# Rumyantsev.net
KiCad netlist of a schematic drawn in EasyEDA
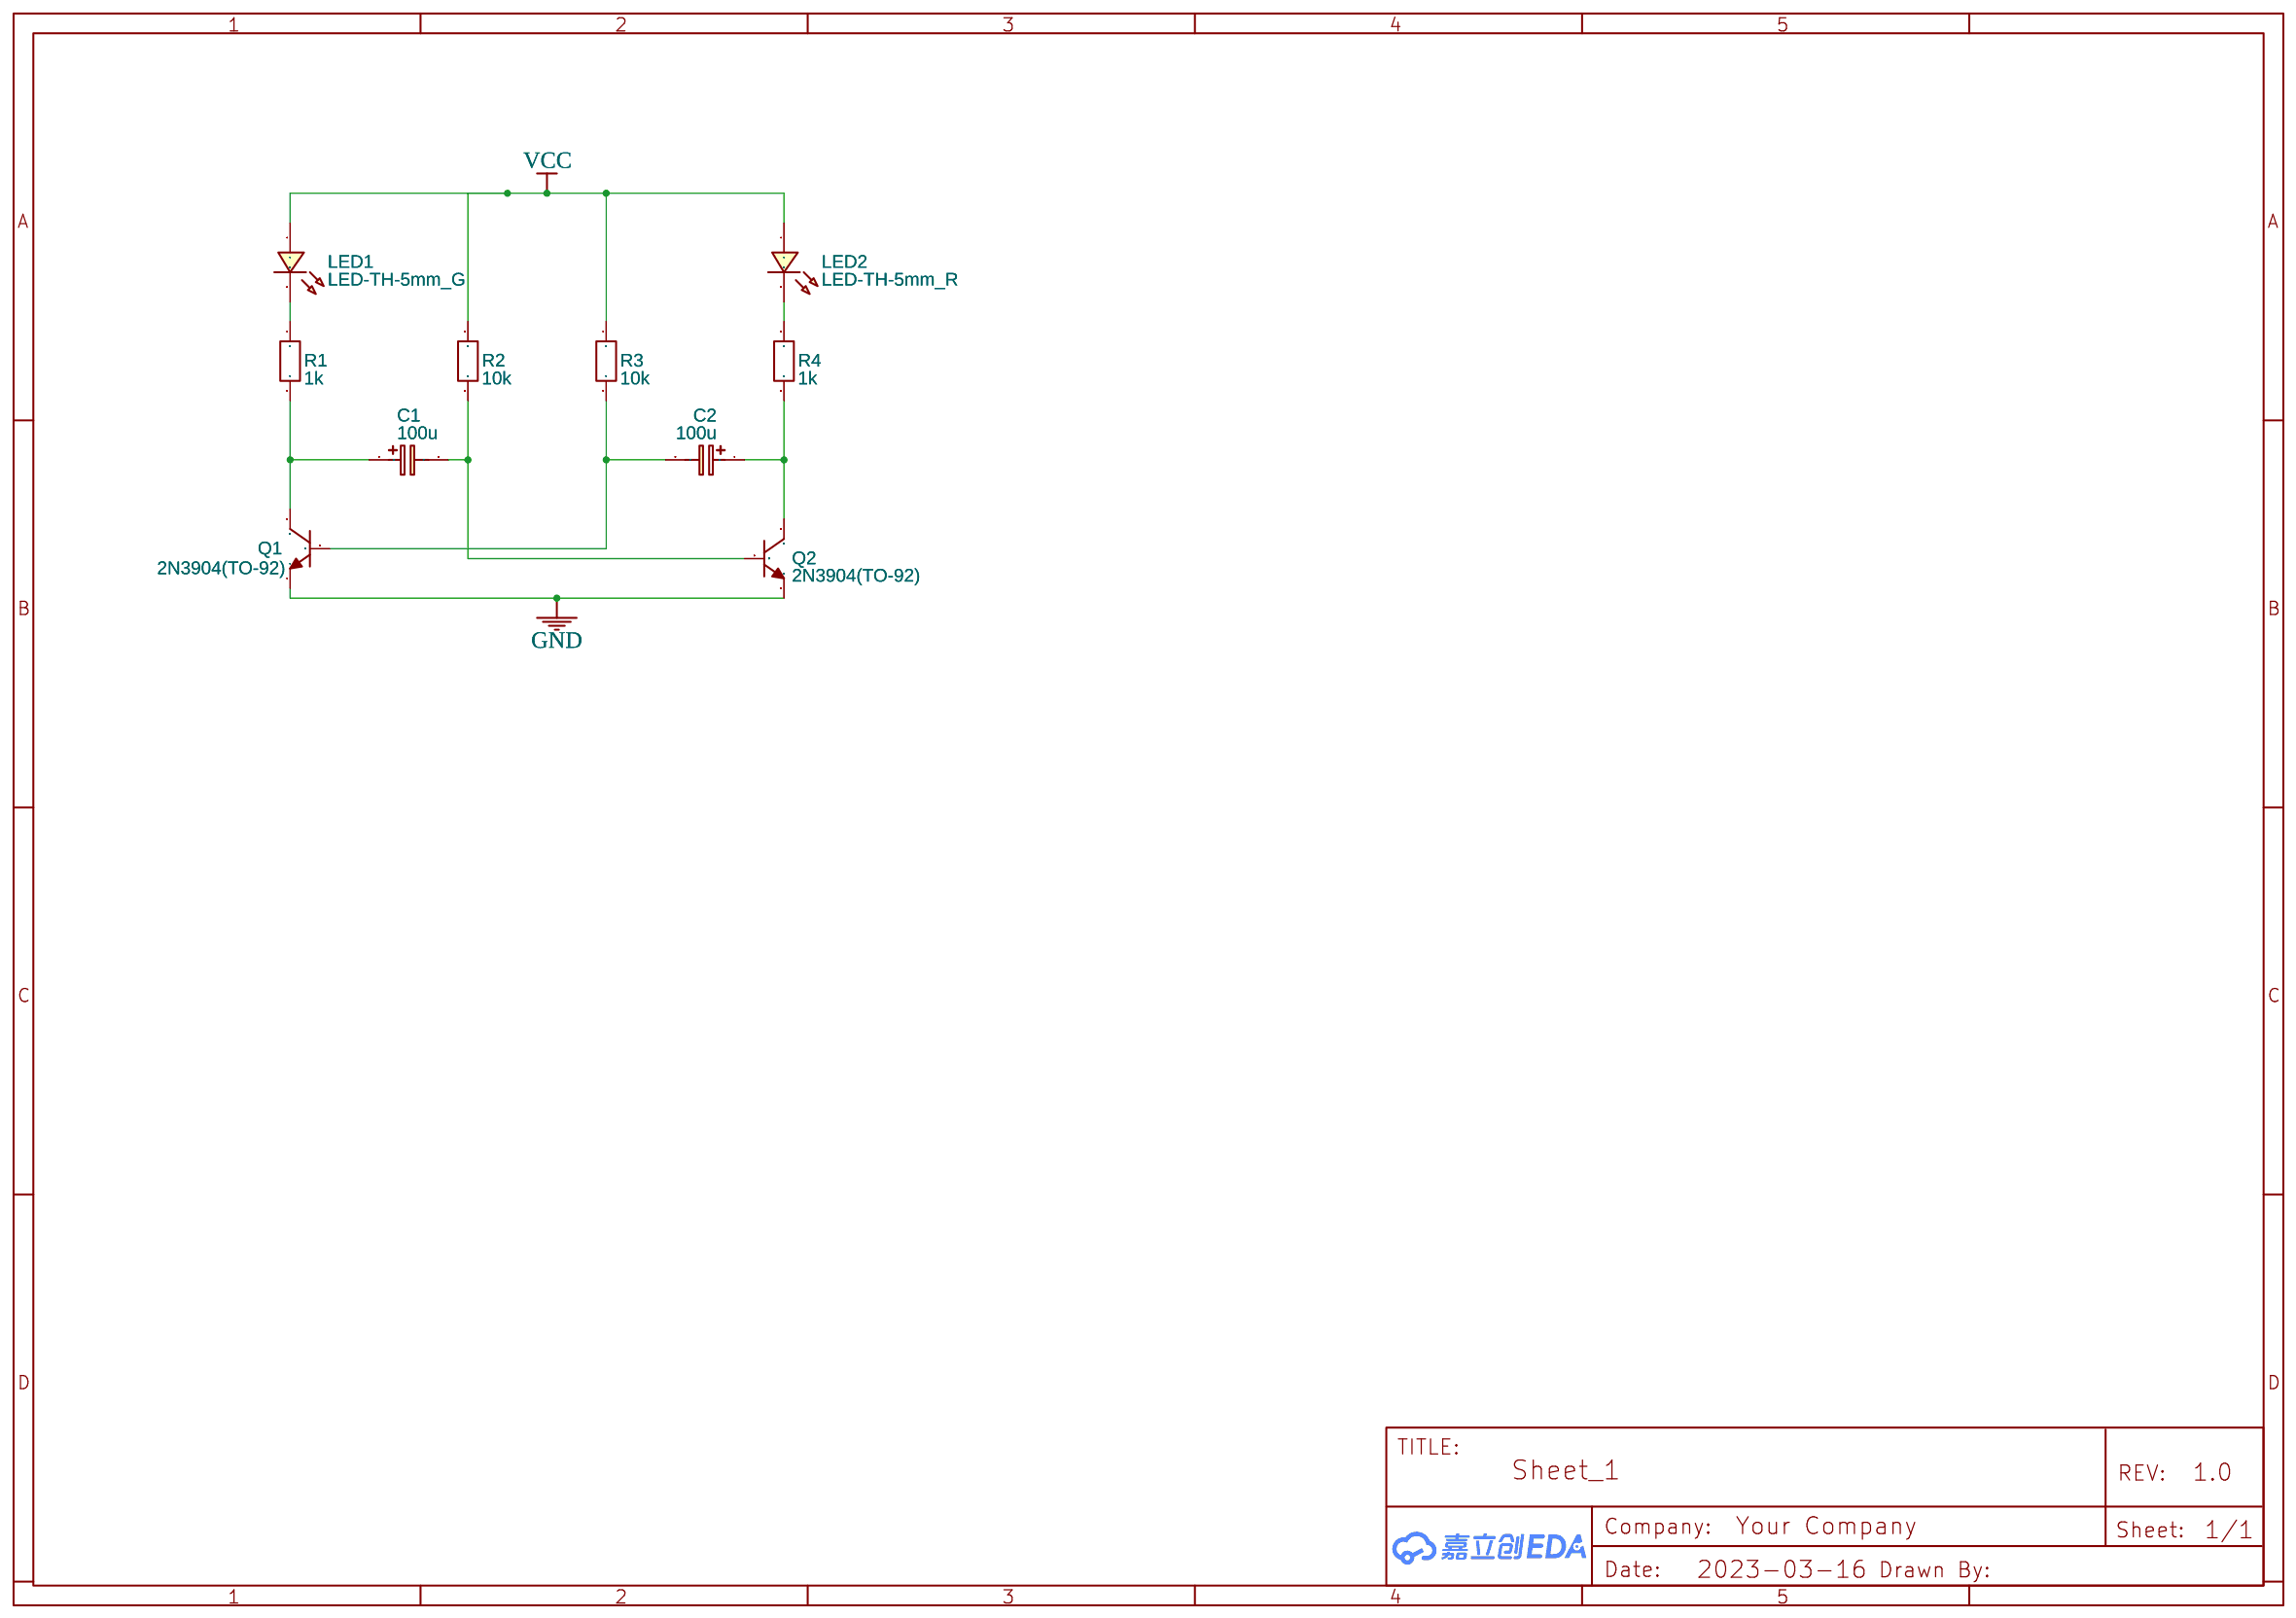
[diagram p0: schematic sheet]

(export (version "E")
  (design (tool "Eeschema 10.0.6"))
  (components
    (comp (ref "C1") (value "100u") (libsource (lib "") (part "CE_TH_D6.3×F2.5_EU")))
    (comp (ref "C2") (value "100u") (libsource (lib "") (part "CE_TH_D6.3×F2.5_EU_1")))
    (comp (ref "LED1")
      (value "LED-TH-5mm_G")
      (fields
        (field (name "BOM_Manufacturer Part") "333-2SYGD/S530-E2")
        (field (name "BOM_Supplier Part") "C88163")
      )
      (libsource (lib "") (part "LED-TH-5mm_G"))
    )
    (comp (ref "LED2")
      (value "LED-TH-5mm_R")
      (fields
        (field (name "BOM_Manufacturer Part") "333-2SURD/S530-A3")
        (field (name "BOM_Supplier Part") "C87271")
      )
      (libsource (lib "") (part "LED-TH-5mm_R"))
    )
    (comp (ref "Q1")
      (value "2N3904(TO-92)")
      (fields (field (name "BOM_Manufacturer Part") "2N3904") (field (name "BOM_Supplier Part") "C118538"))
      (libsource (lib "") (part "2N3904(TO-92)_1"))
    )
    (comp (ref "Q2")
      (value "2N3904(TO-92)")
      (fields (field (name "BOM_Manufacturer Part") "2N3904") (field (name "BOM_Supplier Part") "C118538"))
      (libsource (lib "") (part "2N3904(TO-92)"))
    )
    (comp (ref "R1") (value "1k") (libsource (lib "") (part "R_AXIAL-0.4_EU")))
    (comp (ref "R2") (value "10k") (libsource (lib "") (part "R_AXIAL-0.4_EU")))
    (comp (ref "R3") (value "10k") (libsource (lib "") (part "R_AXIAL-0.4_EU")))
    (comp (ref "R4") (value "1k") (libsource (lib "") (part "R_AXIAL-0.4_EU")))
  )
  (nets
    (net (code "1") (name "GND") (class "Default")
      (node (ref "Q1") (pin "1") (pinfunction "E_1") (pintype "unspecified"))
      (node (ref "Q2") (pin "1") (pinfunction "E_1") (pintype "unspecified"))
    )
    (net (code "2") (name "Net-(LED1-Pad2)") (class "Default")
      (node (ref "LED1") (pin "2") (pinfunction "2_2") (pintype "unspecified"))
      (node (ref "R1") (pin "1") (pinfunction "1_1") (pintype "unspecified"))
    )
    (net (code "3") (name "Net-(LED2-Pad2)") (class "Default")
      (node (ref "LED2") (pin "2") (pinfunction "2_2") (pintype "unspecified"))
      (node (ref "R4") (pin "1") (pinfunction "1_1") (pintype "unspecified"))
    )
    (net (code "4") (name "Net-(Q1-B)") (class "Default")
      (node (ref "C2") (pin "2") (pinfunction "2_2") (pintype "unspecified"))
      (node (ref "Q1") (pin "2") (pinfunction "B_2") (pintype "unspecified"))
      (node (ref "R3") (pin "2") (pinfunction "2_2") (pintype "unspecified"))
    )
    (net (code "5") (name "Net-(Q1-C)") (class "Default")
      (node (ref "C1") (pin "1") (pinfunction "1_1") (pintype "unspecified"))
      (node (ref "Q1") (pin "3") (pinfunction "C_3") (pintype "unspecified"))
      (node (ref "R1") (pin "2") (pinfunction "2_2") (pintype "unspecified"))
    )
    (net (code "6") (name "Net-(Q2-B)") (class "Default")
      (node (ref "C1") (pin "2") (pinfunction "2_2") (pintype "unspecified"))
      (node (ref "Q2") (pin "2") (pinfunction "B_2") (pintype "unspecified"))
      (node (ref "R2") (pin "2") (pinfunction "2_2") (pintype "unspecified"))
    )
    (net (code "7") (name "Net-(Q2-C)") (class "Default")
      (node (ref "C2") (pin "1") (pinfunction "1_1") (pintype "unspecified"))
      (node (ref "Q2") (pin "3") (pinfunction "C_3") (pintype "unspecified"))
      (node (ref "R4") (pin "2") (pinfunction "2_2") (pintype "unspecified"))
    )
    (net (code "8") (name "VCC") (class "Default")
      (node (ref "LED1") (pin "1") (pinfunction "1_1") (pintype "unspecified"))
      (node (ref "LED2") (pin "1") (pinfunction "1_1") (pintype "unspecified"))
      (node (ref "R2") (pin "1") (pinfunction "1_1") (pintype "unspecified"))
      (node (ref "R3") (pin "1") (pinfunction "1_1") (pintype "unspecified"))
    )
  )
)
